# welder_pcb.net
KiCad netlist of a schematic drawn in EAGLE
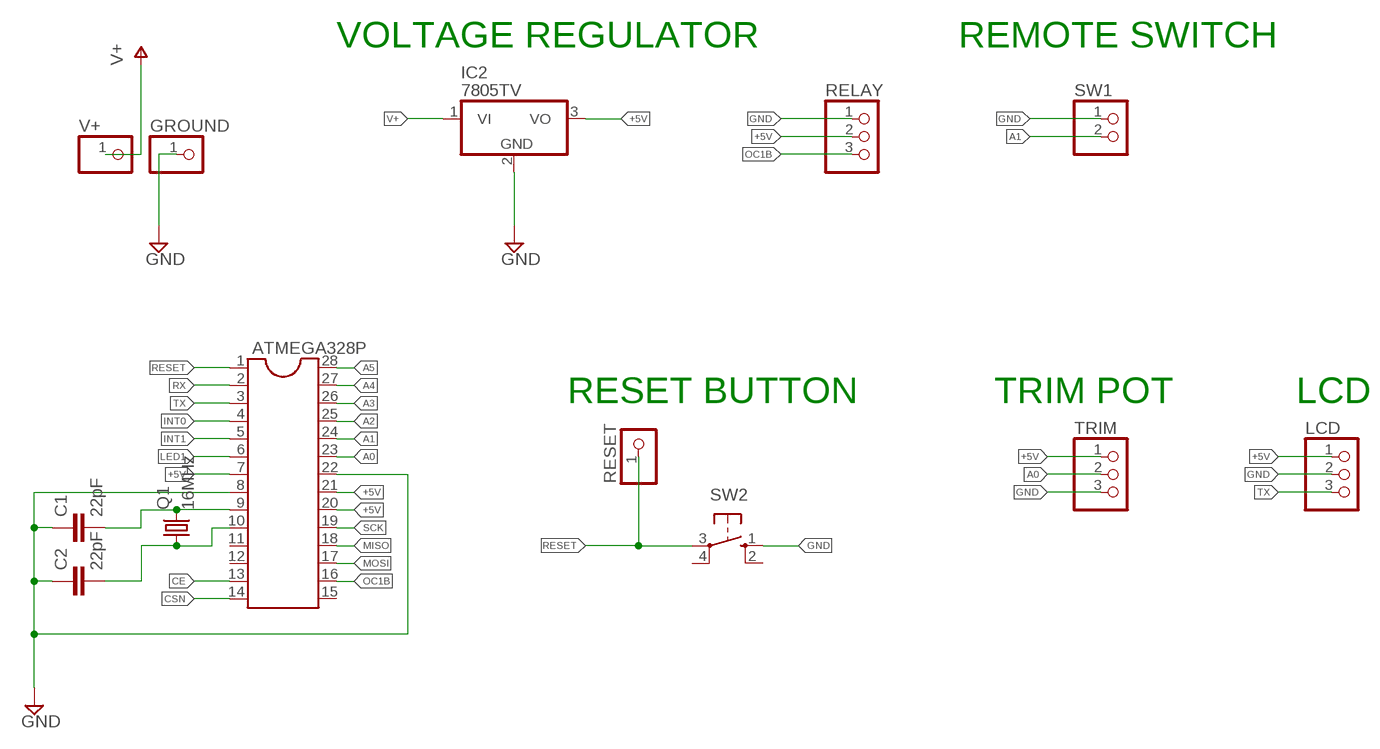
[diagram p0: schematic, sheet 1]

(export (version "E")
  (design (tool "Eeschema 10.0.6"))
  (components
    (comp (ref "ATMEGA328P")
      (value "DIL28-3")
      (footprint "eagle-import:DIL28-3")
      (libsource (lib "eagle-import") (part "DIL28-3"))
    )
    (comp (ref "C1")
      (value "22pF")
      (footprint "eagle-import:C2.5-3")
      (libsource (lib "eagle-import") (part "C2,5-3"))
    )
    (comp (ref "C2")
      (value "22pF")
      (footprint "eagle-import:C2.5-3")
      (libsource (lib "eagle-import") (part "C2,5-3"))
    )
    (comp (ref "GROUND")
      (value "PINHD-1X1")
      (footprint "eagle-import:1X01")
      (libsource (lib "eagle-import") (part "PINHD-1X1"))
    )
    (comp (ref "IC2")
      (value "7805TV")
      (footprint "eagle-import:TO220V")
      (libsource (lib "eagle-import") (part "78TV05"))
    )
    (comp (ref "LCD")
      (value "PINHD-1X3")
      (footprint "eagle-import:1X03")
      (libsource (lib "eagle-import") (part "PINHD-1X3"))
    )
    (comp (ref "Q1")
      (value "16MHz")
      (footprint "eagle-import:HC49U-V")
      (libsource (lib "eagle-import") (part "CRYSTALHC49U-V"))
    )
    (comp (ref "RELAY")
      (value "PINHD-1X3")
      (footprint "eagle-import:1X03")
      (libsource (lib "eagle-import") (part "PINHD-1X3"))
    )
    (comp (ref "RESET")
      (value "PINHD-1X1")
      (footprint "eagle-import:1X01")
      (libsource (lib "eagle-import") (part "pinhead_325_PINHD-1X1"))
    )
    (comp (ref "SW1")
      (value "PINHD-1X2")
      (footprint "eagle-import:1X02")
      (libsource (lib "eagle-import") (part "PINHD-1X2"))
    )
    (comp (ref "SW2")
      (value "10-XX")
      (footprint "eagle-import:B3F-10XX")
      (fields (field (name "MPN") "B3F-1000"))
      (libsource (lib "eagle-import") (part "10-XX"))
    )
    (comp (ref "TRIM")
      (value "PINHD-1X3")
      (footprint "eagle-import:1X03")
      (libsource (lib "eagle-import") (part "PINHD-1X3"))
    )
    (comp (ref "V+")
      (value "PINHD-1X1")
      (footprint "eagle-import:1X01")
      (libsource (lib "eagle-import") (part "PINHD-1X1"))
    )
  )
  (nets
    (net (code "1") (name "+5V") (class "Default")
      (node (ref "ATMEGA328P") (pin "20") (pinfunction "20_20") (pintype "passive"))
      (node (ref "ATMEGA328P") (pin "21") (pinfunction "21_21") (pintype "passive"))
      (node (ref "ATMEGA328P") (pin "7") (pinfunction "7_7") (pintype "passive"))
      (node (ref "IC2") (pin "3") (pinfunction "VO_3") (pintype "passive"))
      (node (ref "LCD") (pin "1") (pinfunction "1_1") (pintype "passive"))
      (node (ref "RELAY") (pin "2") (pinfunction "2_2") (pintype "passive"))
      (node (ref "TRIM") (pin "1") (pinfunction "1_1") (pintype "passive"))
    )
    (net (code "2") (name "A0") (class "Default")
      (node (ref "ATMEGA328P") (pin "23") (pinfunction "23_23") (pintype "passive"))
      (node (ref "TRIM") (pin "2") (pinfunction "2_2") (pintype "passive"))
    )
    (net (code "3") (name "A1") (class "Default")
      (node (ref "ATMEGA328P") (pin "24") (pinfunction "24_24") (pintype "passive"))
      (node (ref "SW1") (pin "2") (pinfunction "2_2") (pintype "passive"))
    )
    (net (code "4") (name "A2") (class "Default")
      (node (ref "ATMEGA328P") (pin "25") (pinfunction "25_25") (pintype "passive"))
    )
    (net (code "5") (name "A3") (class "Default")
      (node (ref "ATMEGA328P") (pin "26") (pinfunction "26_26") (pintype "passive"))
    )
    (net (code "6") (name "A4") (class "Default")
      (node (ref "ATMEGA328P") (pin "27") (pinfunction "27_27") (pintype "passive"))
    )
    (net (code "7") (name "A5") (class "Default")
      (node (ref "ATMEGA328P") (pin "28") (pinfunction "28_28") (pintype "passive"))
    )
    (net (code "8") (name "CE") (class "Default")
      (node (ref "ATMEGA328P") (pin "13") (pinfunction "13_13") (pintype "passive"))
    )
    (net (code "9") (name "CSN") (class "Default")
      (node (ref "ATMEGA328P") (pin "14") (pinfunction "14_14") (pintype "passive"))
    )
    (net (code "10") (name "GND") (class "Default")
      (node (ref "ATMEGA328P") (pin "22") (pinfunction "22_22") (pintype "passive"))
      (node (ref "ATMEGA328P") (pin "8") (pinfunction "8_8") (pintype "passive"))
      (node (ref "C1") (pin "1") (pinfunction "1_1") (pintype "passive"))
      (node (ref "C2") (pin "1") (pinfunction "1_1") (pintype "passive"))
      (node (ref "GROUND") (pin "1") (pinfunction "1_1") (pintype "passive"))
      (node (ref "IC2") (pin "2") (pinfunction "GND_2") (pintype "passive"))
      (node (ref "LCD") (pin "2") (pinfunction "2_2") (pintype "passive"))
      (node (ref "RELAY") (pin "1") (pinfunction "1_1") (pintype "passive"))
      (node (ref "SW1") (pin "1") (pinfunction "1_1") (pintype "passive"))
      (node (ref "SW2") (pin "1") (pinfunction "S_1") (pintype "passive"))
      (node (ref "TRIM") (pin "3") (pinfunction "3_3") (pintype "passive"))
    )
    (net (code "11") (name "INT0") (class "Default")
      (node (ref "ATMEGA328P") (pin "4") (pinfunction "4_4") (pintype "passive"))
    )
    (net (code "12") (name "INT1") (class "Default")
      (node (ref "ATMEGA328P") (pin "5") (pinfunction "5_5") (pintype "passive"))
    )
    (net (code "13") (name "LED1") (class "Default")
      (node (ref "ATMEGA328P") (pin "6") (pinfunction "6_6") (pintype "passive"))
    )
    (net (code "14") (name "MISO") (class "Default")
      (node (ref "ATMEGA328P") (pin "18") (pinfunction "18_18") (pintype "passive"))
    )
    (net (code "15") (name "MOSI") (class "Default")
      (node (ref "ATMEGA328P") (pin "17") (pinfunction "17_17") (pintype "passive"))
    )
    (net (code "16") (name "Net-(ATMEGA328P-Pad9)") (class "Default")
      (node (ref "ATMEGA328P") (pin "9") (pinfunction "9_9") (pintype "passive"))
      (node (ref "C1") (pin "2") (pinfunction "2_2") (pintype "passive"))
      (node (ref "Q1") (pin "2") (pinfunction "2_2") (pintype "passive"))
    )
    (net (code "17") (name "Net-(ATMEGA328P-Pad10)") (class "Default")
      (node (ref "ATMEGA328P") (pin "10") (pinfunction "10_10") (pintype "passive"))
      (node (ref "C2") (pin "2") (pinfunction "2_2") (pintype "passive"))
      (node (ref "Q1") (pin "1") (pinfunction "1_1") (pintype "passive"))
    )
    (net (code "18") (name "OC1B") (class "Default")
      (node (ref "ATMEGA328P") (pin "16") (pinfunction "16_16") (pintype "passive"))
      (node (ref "RELAY") (pin "3") (pinfunction "3_3") (pintype "passive"))
    )
    (net (code "19") (name "RESET") (class "Default")
      (node (ref "ATMEGA328P") (pin "1") (pinfunction "1_1") (pintype "passive"))
      (node (ref "RESET") (pin "1") (pinfunction "1_1") (pintype "passive"))
      (node (ref "SW2") (pin "3") (pinfunction "P_3") (pintype "passive"))
    )
    (net (code "20") (name "RX") (class "Default")
      (node (ref "ATMEGA328P") (pin "2") (pinfunction "2_2") (pintype "passive"))
    )
    (net (code "21") (name "SCK") (class "Default")
      (node (ref "ATMEGA328P") (pin "19") (pinfunction "19_19") (pintype "passive"))
    )
    (net (code "22") (name "TX") (class "Default")
      (node (ref "ATMEGA328P") (pin "3") (pinfunction "3_3") (pintype "passive"))
      (node (ref "LCD") (pin "3") (pinfunction "3_3") (pintype "passive"))
    )
    (net (code "23") (name "V+") (class "Default")
      (node (ref "IC2") (pin "1") (pinfunction "VI_1") (pintype "input"))
      (node (ref "V+") (pin "1") (pinfunction "1_1") (pintype "passive"))
    )
    (net (code "24") (name "unconnected-(ATMEGA328P-Pad11)") (class "Default")
      (node (ref "ATMEGA328P") (pin "11") (pinfunction "11_11") (pintype "passive"))
    )
    (net (code "25") (name "unconnected-(ATMEGA328P-Pad12)") (class "Default")
      (node (ref "ATMEGA328P") (pin "12") (pinfunction "12_12") (pintype "passive"))
    )
    (net (code "26") (name "unconnected-(ATMEGA328P-Pad15)") (class "Default")
      (node (ref "ATMEGA328P") (pin "15") (pinfunction "15_15") (pintype "passive"))
    )
    (net (code "27") (name "unconnected-(SW2-P1-Pad4)") (class "Default")
      (node (ref "SW2") (pin "4") (pinfunction "P1_4") (pintype "passive"))
    )
    (net (code "28") (name "unconnected-(SW2-S1-Pad2)") (class "Default")
      (node (ref "SW2") (pin "2") (pinfunction "S1_2") (pintype "passive"))
    )
  )
)
